# Scheduler_2021-07-28_12-27-31.net
KiCad netlist of a schematic drawn in EasyEDA
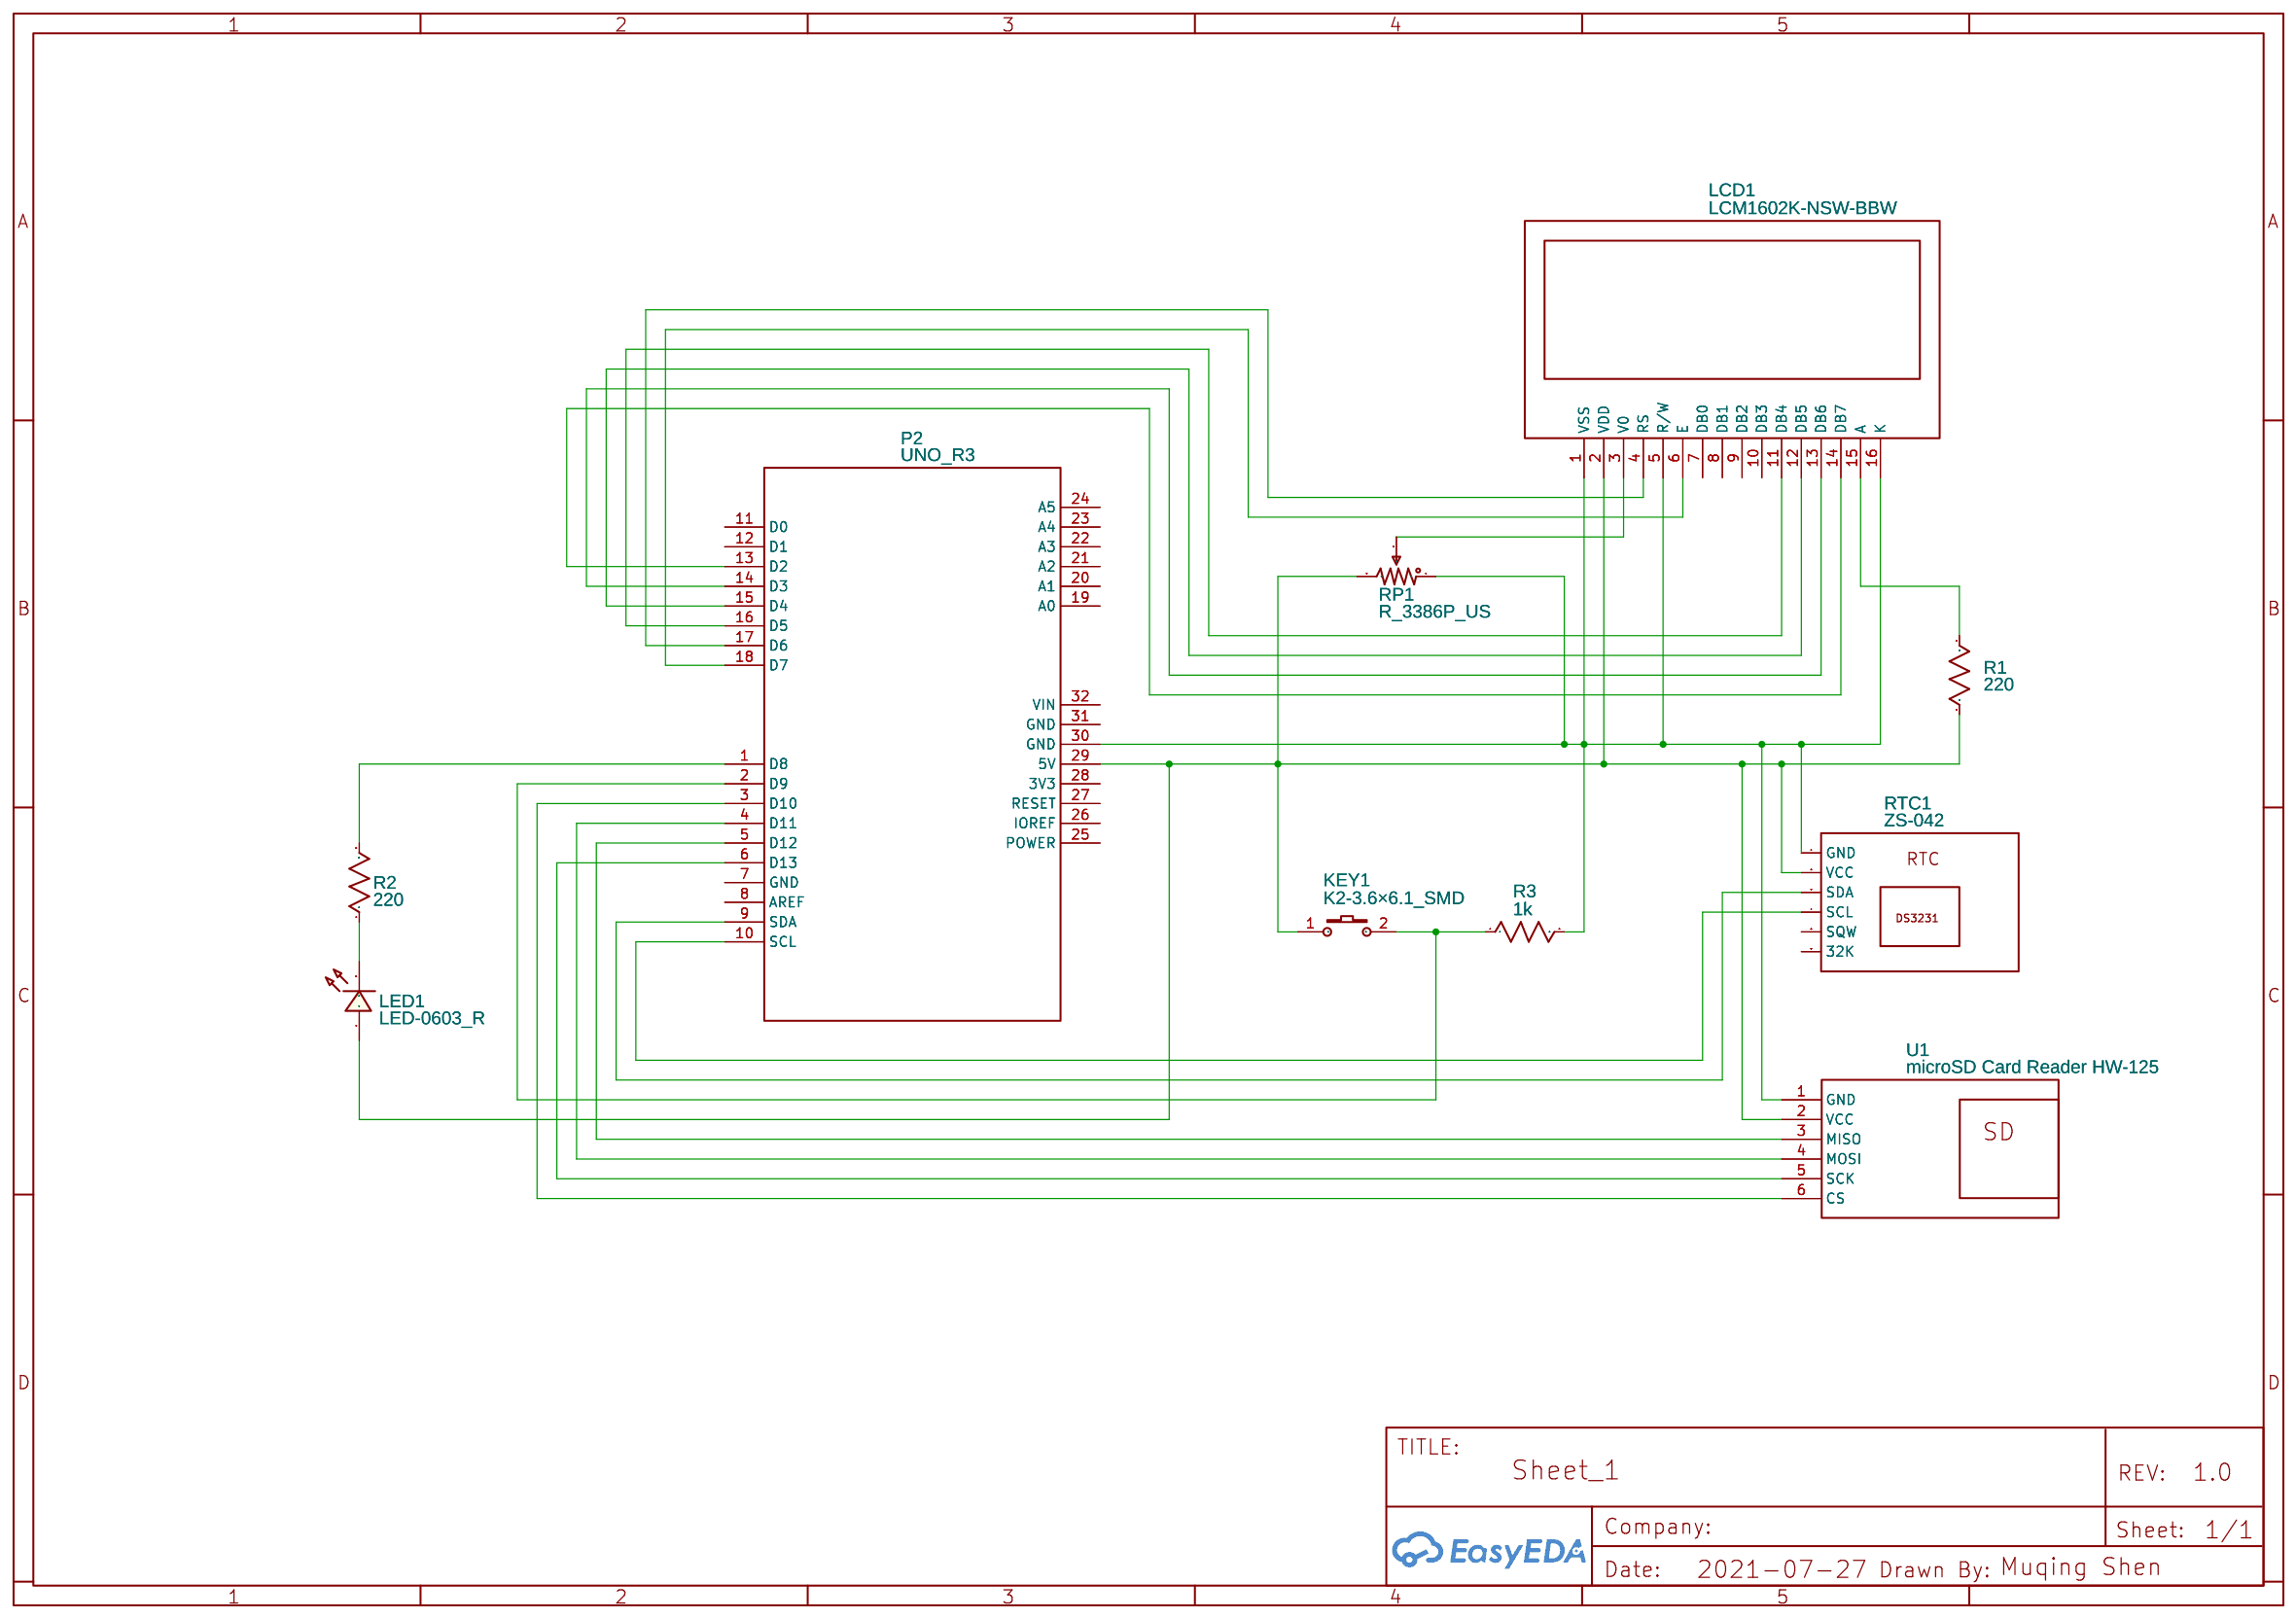
[diagram p0: schematic sheet]

(export (version "E")
  (design (tool "Eeschema 10.0.6"))
  (components
    (comp (ref "KEY1")
      (value "K2-3.6×6.1_SMD")
      (fields
        (field (name "BOM_Manufacturer Part") "K2-1107ST-A4SW-06")
        (field (name "BOM_Supplier Part") "C118141")
      )
      (libsource (lib "") (part "K2-3.6×6.1_SMD"))
    )
    (comp (ref "LCD1")
      (value "LCM1602K-NSW-BBW")
      (fields (field (name "BOM_Supplier Part") "C83275"))
      (libsource (lib "") (part "LCM1602K-NSW-BBW"))
    )
    (comp (ref "LED1")
      (value "LED-0603_R")
      (fields
        (field (name "BOM_Manufacturer Part") "19-217/R6C-AL1M2VY/3T")
        (field (name "BOM_Supplier Part") "C72044")
      )
      (libsource (lib "") (part "LED-0603_R"))
    )
    (comp (ref "P2") (value "UNO_R3") (libsource (lib "") (part "UNO_R3")))
    (comp (ref "R1") (value "220") (libsource (lib "") (part "R_0603_US")))
    (comp (ref "R2") (value "220") (libsource (lib "") (part "R_0603_US")))
    (comp (ref "R3") (value "1k") (libsource (lib "") (part "R_0603_US_1")))
    (comp (ref "RP1") (value "R_3386P_US") (libsource (lib "") (part "R_3386P_US")))
    (comp (ref "RTC1") (value "ZS-042") (libsource (lib "") (part "ZS-042")))
    (comp (ref "U1")
      (value "microSD Card Reader HW-125")
      (libsource (lib "") (part "microSD Card Reader HW-125"))
    )
  )
  (nets
    (net (code "1") (name "Net-(LCD1-A)") (class "Default")
      (node (ref "LCD1") (pin "15") (pinfunction "A_15") (pintype "unspecified"))
      (node (ref "R1") (pin "2") (pinfunction "2_2") (pintype "unspecified"))
    )
    (net (code "2") (name "Net-(LCD1-DB4)") (class "Default")
      (node (ref "LCD1") (pin "11") (pinfunction "DB4_11") (pintype "unspecified"))
      (node (ref "P2") (pin "16") (pinfunction "D5_16") (pintype "unspecified"))
    )
    (net (code "3") (name "Net-(LCD1-DB5)") (class "Default")
      (node (ref "LCD1") (pin "12") (pinfunction "DB5_12") (pintype "unspecified"))
      (node (ref "P2") (pin "15") (pinfunction "D4_15") (pintype "unspecified"))
    )
    (net (code "4") (name "Net-(LCD1-DB6)") (class "Default")
      (node (ref "LCD1") (pin "13") (pinfunction "DB6_13") (pintype "unspecified"))
      (node (ref "P2") (pin "14") (pinfunction "D3_14") (pintype "unspecified"))
    )
    (net (code "5") (name "Net-(LCD1-DB7)") (class "Default")
      (node (ref "LCD1") (pin "14") (pinfunction "DB7_14") (pintype "unspecified"))
      (node (ref "P2") (pin "13") (pinfunction "D2_13") (pintype "unspecified"))
    )
    (net (code "6") (name "Net-(LCD1-E)") (class "Default")
      (node (ref "LCD1") (pin "6") (pinfunction "E_6") (pintype "unspecified"))
      (node (ref "P2") (pin "18") (pinfunction "D7_18") (pintype "unspecified"))
    )
    (net (code "7") (name "Net-(LCD1-K)") (class "Default")
      (node (ref "LCD1") (pin "1") (pinfunction "VSS_1") (pintype "unspecified"))
      (node (ref "LCD1") (pin "16") (pinfunction "K_16") (pintype "unspecified"))
      (node (ref "LCD1") (pin "5") (pinfunction "R/W_5") (pintype "unspecified"))
      (node (ref "P2") (pin "30") (pinfunction "GND_30") (pintype "unspecified"))
      (node (ref "R3") (pin "2") (pinfunction "2_2") (pintype "unspecified"))
      (node (ref "RP1") (pin "1") (pinfunction "1_1") (pintype "unspecified"))
      (node (ref "RTC1") (pin "1") (pinfunction "GND_1") (pintype "passive"))
      (node (ref "U1") (pin "1") (pinfunction "GND_1") (pintype "unspecified"))
    )
    (net (code "8") (name "Net-(LCD1-RS)") (class "Default")
      (node (ref "LCD1") (pin "4") (pinfunction "RS_4") (pintype "unspecified"))
      (node (ref "P2") (pin "17") (pinfunction "D6_17") (pintype "unspecified"))
    )
    (net (code "9") (name "Net-(LCD1-V0)") (class "Default")
      (node (ref "LCD1") (pin "3") (pinfunction "V0_3") (pintype "unspecified"))
      (node (ref "RP1") (pin "2") (pinfunction "2_2") (pintype "unspecified"))
    )
    (net (code "10") (name "Net-(LCD1-VDD)") (class "Default")
      (node (ref "KEY1") (pin "1") (pinfunction "1_1") (pintype "unspecified"))
      (node (ref "LCD1") (pin "2") (pinfunction "VDD_2") (pintype "unspecified"))
      (node (ref "LED1") (pin "1") (pinfunction "1_1") (pintype "unspecified"))
      (node (ref "P2") (pin "29") (pinfunction "5V_29") (pintype "unspecified"))
      (node (ref "R1") (pin "1") (pinfunction "1_1") (pintype "unspecified"))
      (node (ref "RP1") (pin "3") (pinfunction "3_3") (pintype "unspecified"))
      (node (ref "RTC1") (pin "2") (pinfunction "VCC_2") (pintype "passive"))
      (node (ref "U1") (pin "2") (pinfunction "VCC_2") (pintype "unspecified"))
    )
    (net (code "11") (name "Net-(LED1-Pad2)") (class "Default")
      (node (ref "LED1") (pin "2") (pinfunction "2_2") (pintype "unspecified"))
      (node (ref "R2") (pin "1") (pinfunction "1_1") (pintype "unspecified"))
    )
    (net (code "12") (name "Net-(P2-D8)") (class "Default")
      (node (ref "P2") (pin "1") (pinfunction "D8_1") (pintype "unspecified"))
      (node (ref "R2") (pin "2") (pinfunction "2_2") (pintype "unspecified"))
    )
    (net (code "13") (name "Net-(P2-D9)") (class "Default")
      (node (ref "KEY1") (pin "2") (pinfunction "2_2") (pintype "unspecified"))
      (node (ref "P2") (pin "2") (pinfunction "D9_2") (pintype "unspecified"))
      (node (ref "R3") (pin "1") (pinfunction "1_1") (pintype "unspecified"))
    )
    (net (code "14") (name "Net-(P2-D10)") (class "Default")
      (node (ref "P2") (pin "3") (pinfunction "D10_3") (pintype "unspecified"))
      (node (ref "U1") (pin "6") (pinfunction "CS_6") (pintype "unspecified"))
    )
    (net (code "15") (name "Net-(P2-D11)") (class "Default")
      (node (ref "P2") (pin "4") (pinfunction "D11_4") (pintype "unspecified"))
      (node (ref "U1") (pin "4") (pinfunction "MOSI_4") (pintype "unspecified"))
    )
    (net (code "16") (name "Net-(P2-D12)") (class "Default")
      (node (ref "P2") (pin "5") (pinfunction "D12_5") (pintype "unspecified"))
      (node (ref "U1") (pin "3") (pinfunction "MISO_3") (pintype "unspecified"))
    )
    (net (code "17") (name "Net-(P2-D13)") (class "Default")
      (node (ref "P2") (pin "6") (pinfunction "D13_6") (pintype "unspecified"))
      (node (ref "U1") (pin "5") (pinfunction "SCK_5") (pintype "unspecified"))
    )
    (net (code "18") (name "Net-(P2-SCL)") (class "Default")
      (node (ref "P2") (pin "10") (pinfunction "SCL_10") (pintype "unspecified"))
      (node (ref "RTC1") (pin "4") (pinfunction "SCL_4") (pintype "unspecified"))
    )
    (net (code "19") (name "Net-(P2-SDA)") (class "Default")
      (node (ref "P2") (pin "9") (pinfunction "SDA_9") (pintype "unspecified"))
      (node (ref "RTC1") (pin "3") (pinfunction "SDA_3") (pintype "bidirectional"))
    )
    (net (code "20") (name "unconnected-(LCD1-DB0-Pad7)") (class "Default")
      (node (ref "LCD1") (pin "7") (pinfunction "DB0_7") (pintype "unspecified"))
    )
    (net (code "21") (name "unconnected-(LCD1-DB1-Pad8)") (class "Default")
      (node (ref "LCD1") (pin "8") (pinfunction "DB1_8") (pintype "unspecified"))
    )
    (net (code "22") (name "unconnected-(LCD1-DB2-Pad9)") (class "Default")
      (node (ref "LCD1") (pin "9") (pinfunction "DB2_9") (pintype "unspecified"))
    )
    (net (code "23") (name "unconnected-(LCD1-DB3-Pad10)") (class "Default")
      (node (ref "LCD1") (pin "10") (pinfunction "DB3_10") (pintype "unspecified"))
    )
    (net (code "24") (name "unconnected-(P2-3V3-Pad28)") (class "Default")
      (node (ref "P2") (pin "28") (pinfunction "3V3_28") (pintype "unspecified"))
    )
    (net (code "25") (name "unconnected-(P2-A0-Pad19)") (class "Default")
      (node (ref "P2") (pin "19") (pinfunction "A0_19") (pintype "unspecified"))
    )
    (net (code "26") (name "unconnected-(P2-A1-Pad20)") (class "Default")
      (node (ref "P2") (pin "20") (pinfunction "A1_20") (pintype "unspecified"))
    )
    (net (code "27") (name "unconnected-(P2-A2-Pad21)") (class "Default")
      (node (ref "P2") (pin "21") (pinfunction "A2_21") (pintype "unspecified"))
    )
    (net (code "28") (name "unconnected-(P2-A3-Pad22)") (class "Default")
      (node (ref "P2") (pin "22") (pinfunction "A3_22") (pintype "unspecified"))
    )
    (net (code "29") (name "unconnected-(P2-A4-Pad23)") (class "Default")
      (node (ref "P2") (pin "23") (pinfunction "A4_23") (pintype "unspecified"))
    )
    (net (code "30") (name "unconnected-(P2-A5-Pad24)") (class "Default")
      (node (ref "P2") (pin "24") (pinfunction "A5_24") (pintype "unspecified"))
    )
    (net (code "31") (name "unconnected-(P2-AREF-Pad8)") (class "Default")
      (node (ref "P2") (pin "8") (pinfunction "AREF_8") (pintype "unspecified"))
    )
    (net (code "32") (name "unconnected-(P2-D0-Pad11)") (class "Default")
      (node (ref "P2") (pin "11") (pinfunction "D0_11") (pintype "unspecified"))
    )
    (net (code "33") (name "unconnected-(P2-D1-Pad12)") (class "Default")
      (node (ref "P2") (pin "12") (pinfunction "D1_12") (pintype "unspecified"))
    )
    (net (code "34") (name "unconnected-(P2-GND-Pad7)") (class "Default")
      (node (ref "P2") (pin "7") (pinfunction "GND_7") (pintype "unspecified"))
    )
    (net (code "35") (name "unconnected-(P2-GND-Pad31)") (class "Default")
      (node (ref "P2") (pin "31") (pinfunction "GND_31") (pintype "unspecified"))
    )
    (net (code "36") (name "unconnected-(P2-IOREF-Pad26)") (class "Default")
      (node (ref "P2") (pin "26") (pinfunction "IOREF_26") (pintype "unspecified"))
    )
    (net (code "37") (name "unconnected-(P2-POWER-Pad25)") (class "Default")
      (node (ref "P2") (pin "25") (pinfunction "POWER_25") (pintype "unspecified"))
    )
    (net (code "38") (name "unconnected-(P2-RESET-Pad27)") (class "Default")
      (node (ref "P2") (pin "27") (pinfunction "RESET_27") (pintype "unspecified"))
    )
    (net (code "39") (name "unconnected-(P2-VIN-Pad32)") (class "Default")
      (node (ref "P2") (pin "32") (pinfunction "VIN_32") (pintype "unspecified"))
    )
    (net (code "40") (name "unconnected-(RTC1-32K-Pad6)") (class "Default")
      (node (ref "RTC1") (pin "6") (pinfunction "32K_6") (pintype "input"))
    )
    (net (code "41") (name "unconnected-(RTC1-SQW-Pad5)") (class "Default")
      (node (ref "RTC1") (pin "5") (pinfunction "SQW_5") (pintype "input"))
    )
  )
)
